# EC_4_Pin_2_0_-_edited.net
KiCad netlist of a schematic drawn in EAGLE
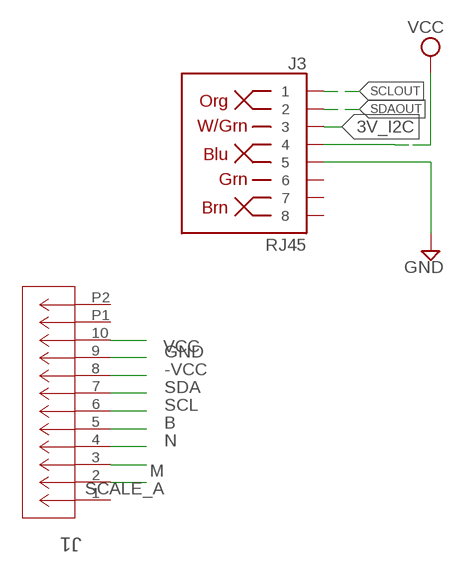
[diagram p0: schematic, sheet 1, part 1 of 2]
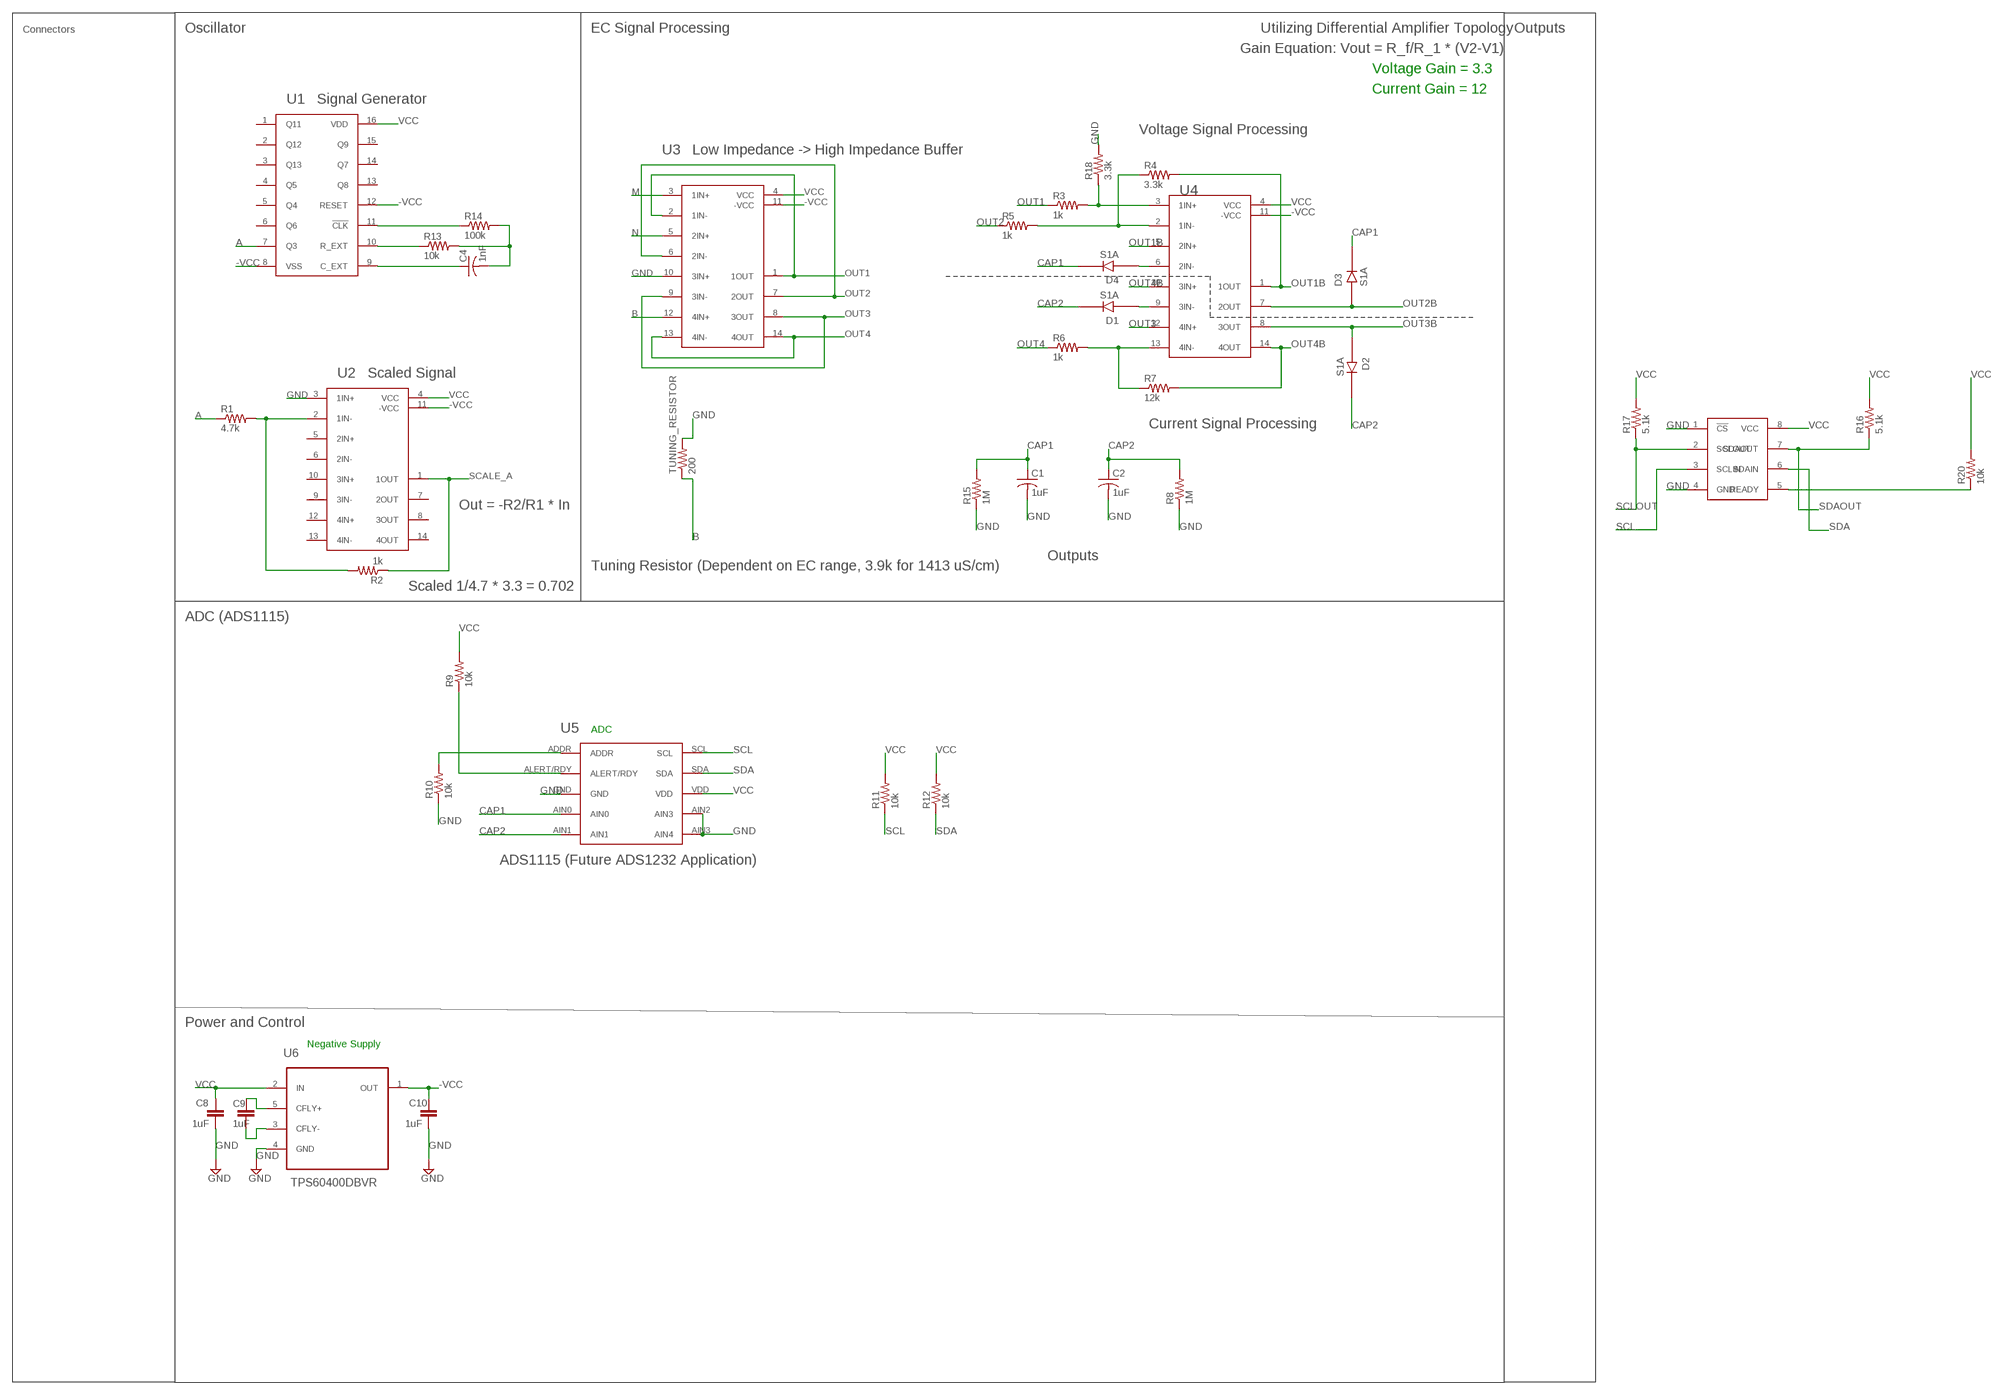
[diagram p1: schematic, sheet 1, part 2 of 2]

(export (version "E")
  (design (tool "Eeschema 10.0.6"))
  (components
    (comp (ref "C1")
      (value "1uF")
      (footprint "eagle-import:C025-024X044")
      (libsource (lib "eagle-import") (part "C-US025-024X044"))
    )
    (comp (ref "C2")
      (value "1uF")
      (footprint "eagle-import:C025-024X044")
      (libsource (lib "eagle-import") (part "C-US025-024X044"))
    )
    (comp (ref "C4")
      (value "1nF")
      (footprint "eagle-import:C1206")
      (libsource (lib "eagle-import") (part "C-USC1206"))
    )
    (comp (ref "C8")
      (value "1uF")
      (footprint "eagle-import:C1206")
      (libsource (lib "eagle-import") (part "C-EUC1206"))
    )
    (comp (ref "C9")
      (value "1uF")
      (footprint "eagle-import:C1206")
      (libsource (lib "eagle-import") (part "C-EUC1206"))
    )
    (comp (ref "C10")
      (value "1uF")
      (footprint "eagle-import:C1206")
      (libsource (lib "eagle-import") (part "C-EUC1206"))
    )
    (comp (ref "D1")
      (value "S1A")
      (footprint "eagle-import:DIOM5227X270N")
      (fields (field (name "DIGI-KEY_PART_NUMBER") "S1AFSTR-ND") (field (name "MF") "ON Semiconductor"))
      (libsource (lib "eagle-import") (part "S1A"))
    )
    (comp (ref "D2")
      (value "S1A")
      (footprint "eagle-import:DIOM5227X270N")
      (fields (field (name "DIGI-KEY_PART_NUMBER") "S1AFSTR-ND") (field (name "MF") "ON Semiconductor"))
      (libsource (lib "eagle-import") (part "S1A"))
    )
    (comp (ref "D3")
      (value "S1A")
      (footprint "eagle-import:DIOM5227X270N")
      (fields (field (name "DIGI-KEY_PART_NUMBER") "S1AFSTR-ND") (field (name "MF") "ON Semiconductor"))
      (libsource (lib "eagle-import") (part "S1A"))
    )
    (comp (ref "D4")
      (value "S1A")
      (footprint "eagle-import:DIOM5227X270N")
      (fields (field (name "DIGI-KEY_PART_NUMBER") "S1AFSTR-ND") (field (name "MF") "ON Semiconductor"))
      (libsource (lib "eagle-import") (part "S1A"))
    )
    (comp (ref "J1")
      (value "522711079")
      (footprint "eagle-import:CON_522711079_MOL")
      (fields (field (name "COPYRIGHT") "Copyright (C) 2023 Ultra Librarian. All rights reserved."))
      (libsource (lib "eagle-import") (part "522711079"))
    )
    (comp (ref "J3")
      (value "RJ45")
      (footprint "eagle-import:RJ45-8")
      (libsource (lib "eagle-import") (part "RJ45-8"))
    )
    (comp (ref "R1")
      (value "4.7k")
      (footprint "eagle-import:M1206")
      (libsource (lib "eagle-import") (part "R-US_M1206"))
    )
    (comp (ref "R2")
      (value "1k")
      (footprint "eagle-import:M1206")
      (libsource (lib "eagle-import") (part "R-US_M1206"))
    )
    (comp (ref "R3")
      (value "1k")
      (footprint "eagle-import:M1206")
      (libsource (lib "eagle-import") (part "R-US_M1206"))
    )
    (comp (ref "R4")
      (value "3.3k")
      (footprint "eagle-import:M1206")
      (libsource (lib "eagle-import") (part "R-US_M1206"))
    )
    (comp (ref "R5")
      (value "1k")
      (footprint "eagle-import:M1206")
      (libsource (lib "eagle-import") (part "R-US_M1206"))
    )
    (comp (ref "R6")
      (value "1k")
      (footprint "eagle-import:M1206")
      (libsource (lib "eagle-import") (part "R-US_M1206"))
    )
    (comp (ref "R7")
      (value "12k")
      (footprint "eagle-import:M1206")
      (libsource (lib "eagle-import") (part "R-US_M1206"))
    )
    (comp (ref "R8")
      (value "1M")
      (footprint "eagle-import:M1206")
      (libsource (lib "eagle-import") (part "R-US_M1206"))
    )
    (comp (ref "R9")
      (value "10k")
      (footprint "eagle-import:M1206")
      (libsource (lib "eagle-import") (part "R-US_M1206"))
    )
    (comp (ref "R10")
      (value "10k")
      (footprint "eagle-import:M1206")
      (libsource (lib "eagle-import") (part "R-US_M1206"))
    )
    (comp (ref "R11")
      (value "10k")
      (footprint "eagle-import:M1206")
      (libsource (lib "eagle-import") (part "R-US_M1206"))
    )
    (comp (ref "R12")
      (value "10k")
      (footprint "eagle-import:M1206")
      (libsource (lib "eagle-import") (part "R-US_M1206"))
    )
    (comp (ref "R13")
      (value "10k")
      (footprint "eagle-import:M1206")
      (libsource (lib "eagle-import") (part "R-US_M1206"))
    )
    (comp (ref "R14")
      (value "100k")
      (footprint "eagle-import:M1206")
      (libsource (lib "eagle-import") (part "R-US_M1206"))
    )
    (comp (ref "R15")
      (value "1M")
      (footprint "eagle-import:M1206")
      (libsource (lib "eagle-import") (part "R-US_M1206"))
    )
    (comp (ref "R16")
      (value "5.1k")
      (footprint "eagle-import:M1206")
      (libsource (lib "eagle-import") (part "R-US_M1206"))
    )
    (comp (ref "R17")
      (value "5.1k")
      (footprint "eagle-import:M1206")
      (libsource (lib "eagle-import") (part "R-US_M1206"))
    )
    (comp (ref "R18")
      (value "3.3k")
      (footprint "eagle-import:M1206")
      (libsource (lib "eagle-import") (part "R-US_M1206"))
    )
    (comp (ref "R20")
      (value "10k")
      (footprint "eagle-import:M1206")
      (libsource (lib "eagle-import") (part "R-US_M1206"))
    )
    (comp (ref "TUNING_RESISTOR")
      (value "200")
      (footprint "eagle-import:M1206")
      (libsource (lib "eagle-import") (part "R-US_M1206"))
    )
    (comp (ref "U$1")
      (value "LTC4301")
      (footprint "eagle-import:LTC4301")
      (libsource (lib "eagle-import") (part "LTC4301"))
    )
    (comp (ref "U1")
      (value "CD4060BPWR")
      (footprint "eagle-import:CD4060BPWR")
      (libsource (lib "eagle-import") (part "CD4060BPWR"))
    )
    (comp (ref "U2")
      (value "TL074CPWR")
      (footprint "eagle-import:LT074CPWR")
      (libsource (lib "eagle-import") (part "TL074CPWR"))
    )
    (comp (ref "U3")
      (value "TL074CPWR")
      (footprint "eagle-import:LT074CPWR")
      (libsource (lib "eagle-import") (part "TL074CPWR"))
    )
    (comp (ref "U4")
      (value "TL074CPWR")
      (footprint "eagle-import:LT074CPWR")
      (libsource (lib "eagle-import") (part "TL074CPWR"))
    )
    (comp (ref "U5")
      (value "ADS1115")
      (footprint "eagle-import:ADS1115")
      (libsource (lib "eagle-import") (part "ADS1115"))
    )
    (comp (ref "U6")
      (value "TPS60400DBVR")
      (footprint "eagle-import:SOT95P280X145-5N")
      (fields (field (name "MF") "Texas Instruments"))
      (libsource (lib "eagle-import") (part "TPS60400DBVR"))
    )
  )
  (nets
    (net (code "1") (name "/-VCC") (class "Default")
      (node (ref "C10") (pin "2") (pinfunction "2_2") (pintype "passive"))
      (node (ref "J1") (pin "8") (pinfunction "8_8") (pintype "passive"))
      (node (ref "U1") (pin "12") (pinfunction "RESET_12") (pintype "bidirectional"))
      (node (ref "U1") (pin "8") (pinfunction "VSS_8") (pintype "bidirectional"))
      (node (ref "U2") (pin "11") (pinfunction "-VCC_11") (pintype "bidirectional"))
      (node (ref "U3") (pin "11") (pinfunction "-VCC_11") (pintype "bidirectional"))
      (node (ref "U4") (pin "11") (pinfunction "-VCC_11") (pintype "bidirectional"))
      (node (ref "U6") (pin "1") (pinfunction "OUT_1") (pintype "output"))
    )
    (net (code "2") (name "/A") (class "Default")
      (node (ref "R1") (pin "1") (pinfunction "1_1") (pintype "passive"))
      (node (ref "U1") (pin "7") (pinfunction "Q3_7") (pintype "bidirectional"))
    )
    (net (code "3") (name "/B") (class "Default")
      (node (ref "J1") (pin "5") (pinfunction "5_5") (pintype "passive"))
      (node (ref "TUNING_RESISTOR") (pin "1") (pinfunction "1_1") (pintype "passive"))
      (node (ref "U3") (pin "12") (pinfunction "4IN+_12") (pintype "bidirectional"))
    )
    (net (code "4") (name "/CAP1") (class "Default")
      (node (ref "C1") (pin "1") (pinfunction "1_1") (pintype "passive"))
      (node (ref "D3") (pin "1") (pinfunction "C_1") (pintype "passive"))
      (node (ref "D4") (pin "1") (pinfunction "C_1") (pintype "passive"))
      (node (ref "R15") (pin "2") (pinfunction "2_2") (pintype "passive"))
      (node (ref "U5") (pin "AIN0") (pinfunction "AIN0_AIN0") (pintype "bidirectional"))
    )
    (net (code "5") (name "/CAP2") (class "Default")
      (node (ref "C2") (pin "1") (pinfunction "1_1") (pintype "passive"))
      (node (ref "D1") (pin "1") (pinfunction "C_1") (pintype "passive"))
      (node (ref "D2") (pin "1") (pinfunction "C_1") (pintype "passive"))
      (node (ref "R8") (pin "2") (pinfunction "2_2") (pintype "passive"))
      (node (ref "U5") (pin "AIN1") (pinfunction "AIN1_AIN1") (pintype "bidirectional"))
    )
    (net (code "6") (name "/M") (class "Default")
      (node (ref "J1") (pin "3") (pinfunction "3_3") (pintype "passive"))
      (node (ref "U3") (pin "3") (pinfunction "1IN+_3") (pintype "bidirectional"))
    )
    (net (code "7") (name "/N") (class "Default")
      (node (ref "J1") (pin "4") (pinfunction "4_4") (pintype "passive"))
      (node (ref "U3") (pin "5") (pinfunction "2IN+_5") (pintype "bidirectional"))
    )
    (net (code "8") (name "/OUT1") (class "Default")
      (node (ref "R3") (pin "1") (pinfunction "1_1") (pintype "passive"))
      (node (ref "U3") (pin "1") (pinfunction "1OUT_1") (pintype "bidirectional"))
      (node (ref "U3") (pin "2") (pinfunction "1IN-_2") (pintype "bidirectional"))
    )
    (net (code "9") (name "/OUT1B") (class "Default")
      (node (ref "R4") (pin "2") (pinfunction "2_2") (pintype "passive"))
      (node (ref "U4") (pin "1") (pinfunction "1OUT_1") (pintype "bidirectional"))
      (node (ref "U4") (pin "5") (pinfunction "2IN+_5") (pintype "bidirectional"))
    )
    (net (code "10") (name "/OUT2") (class "Default")
      (node (ref "R5") (pin "1") (pinfunction "1_1") (pintype "passive"))
      (node (ref "U3") (pin "6") (pinfunction "2IN-_6") (pintype "bidirectional"))
      (node (ref "U3") (pin "7") (pinfunction "2OUT_7") (pintype "bidirectional"))
    )
    (net (code "11") (name "/OUT2B") (class "Default")
      (node (ref "D3") (pin "2") (pinfunction "A_2") (pintype "passive"))
      (node (ref "U4") (pin "7") (pinfunction "2OUT_7") (pintype "bidirectional"))
    )
    (net (code "12") (name "/OUT3") (class "Default")
      (node (ref "U3") (pin "8") (pinfunction "3OUT_8") (pintype "bidirectional"))
      (node (ref "U3") (pin "9") (pinfunction "3IN-_9") (pintype "bidirectional"))
      (node (ref "U4") (pin "12") (pinfunction "4IN+_12") (pintype "bidirectional"))
    )
    (net (code "13") (name "/OUT3B") (class "Default")
      (node (ref "D2") (pin "2") (pinfunction "A_2") (pintype "passive"))
      (node (ref "U4") (pin "8") (pinfunction "3OUT_8") (pintype "bidirectional"))
    )
    (net (code "14") (name "/OUT4") (class "Default")
      (node (ref "R6") (pin "1") (pinfunction "1_1") (pintype "passive"))
      (node (ref "U3") (pin "13") (pinfunction "4IN-_13") (pintype "bidirectional"))
      (node (ref "U3") (pin "14") (pinfunction "4OUT_14") (pintype "bidirectional"))
    )
    (net (code "15") (name "/OUT4B") (class "Default")
      (node (ref "R7") (pin "2") (pinfunction "2_2") (pintype "passive"))
      (node (ref "U4") (pin "10") (pinfunction "3IN+_10") (pintype "bidirectional"))
      (node (ref "U4") (pin "14") (pinfunction "4OUT_14") (pintype "bidirectional"))
    )
    (net (code "16") (name "/SCALE_A") (class "Default")
      (node (ref "J1") (pin "2") (pinfunction "2_2") (pintype "passive"))
      (node (ref "R2") (pin "1") (pinfunction "1_1") (pintype "passive"))
      (node (ref "U2") (pin "1") (pinfunction "1OUT_1") (pintype "bidirectional"))
    )
    (net (code "17") (name "/SCL") (class "Default")
      (node (ref "J1") (pin "6") (pinfunction "6_6") (pintype "passive"))
      (node (ref "R11") (pin "1") (pinfunction "1_1") (pintype "passive"))
      (node (ref "U$1") (pin "3") (pinfunction "SCLIN_3") (pintype "bidirectional"))
      (node (ref "U5") (pin "SCL") (pinfunction "SCL_SCL") (pintype "bidirectional"))
    )
    (net (code "18") (name "/SDA") (class "Default")
      (node (ref "J1") (pin "7") (pinfunction "7_7") (pintype "passive"))
      (node (ref "R12") (pin "1") (pinfunction "1_1") (pintype "passive"))
      (node (ref "U$1") (pin "6") (pinfunction "SDAIN_6") (pintype "bidirectional"))
      (node (ref "U5") (pin "SDA") (pinfunction "SDA_SDA") (pintype "bidirectional"))
    )
    (net (code "19") (name "3V_I2C") (class "Default")
      (node (ref "J3") (pin "3") (pinfunction "3_3") (pintype "bidirectional"))
    )
    (net (code "20") (name "GND") (class "Default")
      (node (ref "C1") (pin "2") (pinfunction "2_2") (pintype "passive"))
      (node (ref "C10") (pin "1") (pinfunction "1_1") (pintype "passive"))
      (node (ref "C2") (pin "2") (pinfunction "2_2") (pintype "passive"))
      (node (ref "C8") (pin "1") (pinfunction "1_1") (pintype "passive"))
      (node (ref "J1") (pin "9") (pinfunction "9_9") (pintype "passive"))
      (node (ref "J3") (pin "5") (pinfunction "5_5") (pintype "bidirectional"))
      (node (ref "R10") (pin "1") (pinfunction "1_1") (pintype "passive"))
      (node (ref "R15") (pin "1") (pinfunction "1_1") (pintype "passive"))
      (node (ref "R18") (pin "2") (pinfunction "2_2") (pintype "passive"))
      (node (ref "R8") (pin "1") (pinfunction "1_1") (pintype "passive"))
      (node (ref "TUNING_RESISTOR") (pin "2") (pinfunction "2_2") (pintype "passive"))
      (node (ref "U$1") (pin "1") (pinfunction "~{CS}_1") (pintype "bidirectional"))
      (node (ref "U$1") (pin "4") (pinfunction "GND_4") (pintype "bidirectional"))
      (node (ref "U2") (pin "3") (pinfunction "1IN+_3") (pintype "bidirectional"))
      (node (ref "U3") (pin "10") (pinfunction "3IN+_10") (pintype "bidirectional"))
      (node (ref "U5") (pin "AIN2") (pinfunction "AIN3_AIN2") (pintype "bidirectional"))
      (node (ref "U5") (pin "AIN3") (pinfunction "AIN4_AIN3") (pintype "bidirectional"))
      (node (ref "U5") (pin "GND") (pinfunction "GND_GND") (pintype "bidirectional"))
      (node (ref "U6") (pin "4") (pinfunction "GND_4") (pintype "passive"))
    )
    (net (code "21") (name "Net-(C4-Pad2)") (class "Default")
      (node (ref "C4") (pin "2") (pinfunction "2_2") (pintype "passive"))
      (node (ref "R13") (pin "2") (pinfunction "2_2") (pintype "passive"))
      (node (ref "R14") (pin "2") (pinfunction "2_2") (pintype "passive"))
    )
    (net (code "22") (name "Net-(D1-A)") (class "Default")
      (node (ref "D1") (pin "2") (pinfunction "A_2") (pintype "passive"))
      (node (ref "U4") (pin "9") (pinfunction "3IN-_9") (pintype "bidirectional"))
    )
    (net (code "23") (name "Net-(D4-A)") (class "Default")
      (node (ref "D4") (pin "2") (pinfunction "A_2") (pintype "passive"))
      (node (ref "U4") (pin "6") (pinfunction "2IN-_6") (pintype "bidirectional"))
    )
    (net (code "24") (name "Net-(R9-Pad1)") (class "Default")
      (node (ref "R9") (pin "1") (pinfunction "1_1") (pintype "passive"))
      (node (ref "U5") (pin "ALERT/RDY") (pinfunction "ALERT/RDY_ALERT/RDY") (pintype "bidirectional"))
    )
    (net (code "25") (name "Net-(R10-Pad2)") (class "Default")
      (node (ref "R10") (pin "2") (pinfunction "2_2") (pintype "passive"))
      (node (ref "U5") (pin "ADDR") (pinfunction "ADDR_ADDR") (pintype "bidirectional"))
    )
    (net (code "26") (name "Net-(U$1-READY)") (class "Default")
      (node (ref "R20") (pin "1") (pinfunction "1_1") (pintype "passive"))
      (node (ref "U$1") (pin "5") (pinfunction "READY_5") (pintype "bidirectional"))
    )
    (net (code "27") (name "Net-(U1-C_EXT)") (class "Default")
      (node (ref "C4") (pin "1") (pinfunction "1_1") (pintype "passive"))
      (node (ref "U1") (pin "9") (pinfunction "C_EXT_9") (pintype "bidirectional"))
    )
    (net (code "28") (name "Net-(U1-R_EXT)") (class "Default")
      (node (ref "R13") (pin "1") (pinfunction "1_1") (pintype "passive"))
      (node (ref "U1") (pin "10") (pinfunction "R_EXT_10") (pintype "bidirectional"))
    )
    (net (code "29") (name "Net-(U1-~{CLK})") (class "Default")
      (node (ref "R14") (pin "1") (pinfunction "1_1") (pintype "passive"))
      (node (ref "U1") (pin "11") (pinfunction "~{CLK}_11") (pintype "bidirectional"))
    )
    (net (code "30") (name "Net-(U2-1IN-)") (class "Default")
      (node (ref "R1") (pin "2") (pinfunction "2_2") (pintype "passive"))
      (node (ref "R2") (pin "2") (pinfunction "2_2") (pintype "passive"))
      (node (ref "U2") (pin "2") (pinfunction "1IN-_2") (pintype "bidirectional"))
    )
    (net (code "31") (name "Net-(U4-1IN+)") (class "Default")
      (node (ref "R18") (pin "1") (pinfunction "1_1") (pintype "passive"))
      (node (ref "R3") (pin "2") (pinfunction "2_2") (pintype "passive"))
      (node (ref "U4") (pin "3") (pinfunction "1IN+_3") (pintype "bidirectional"))
    )
    (net (code "32") (name "Net-(U4-1IN-)") (class "Default")
      (node (ref "R4") (pin "1") (pinfunction "1_1") (pintype "passive"))
      (node (ref "R5") (pin "2") (pinfunction "2_2") (pintype "passive"))
      (node (ref "U4") (pin "2") (pinfunction "1IN-_2") (pintype "bidirectional"))
    )
    (net (code "33") (name "Net-(U4-4IN-)") (class "Default")
      (node (ref "R6") (pin "2") (pinfunction "2_2") (pintype "passive"))
      (node (ref "R7") (pin "1") (pinfunction "1_1") (pintype "passive"))
      (node (ref "U4") (pin "13") (pinfunction "4IN-_13") (pintype "bidirectional"))
    )
    (net (code "34") (name "Net-(U6-CFLY+)") (class "Default")
      (node (ref "C9") (pin "2") (pinfunction "2_2") (pintype "passive"))
      (node (ref "U6") (pin "5") (pinfunction "CFLY+_5") (pintype "input"))
    )
    (net (code "35") (name "Net-(U6-CFLY-)") (class "Default")
      (node (ref "C9") (pin "1") (pinfunction "1_1") (pintype "passive"))
      (node (ref "U6") (pin "3") (pinfunction "CFLY-_3") (pintype "input"))
    )
    (net (code "36") (name "SCLOUT") (class "Default")
      (node (ref "J3") (pin "1") (pinfunction "1_1") (pintype "bidirectional"))
      (node (ref "R17") (pin "1") (pinfunction "1_1") (pintype "passive"))
      (node (ref "U$1") (pin "2") (pinfunction "SCLOUT_2") (pintype "bidirectional"))
    )
    (net (code "37") (name "SDAOUT") (class "Default")
      (node (ref "J3") (pin "2") (pinfunction "2_2") (pintype "bidirectional"))
      (node (ref "R16") (pin "1") (pinfunction "1_1") (pintype "passive"))
      (node (ref "U$1") (pin "7") (pinfunction "SDAOUT_7") (pintype "bidirectional"))
    )
    (net (code "38") (name "VCC") (class "Default")
      (node (ref "C8") (pin "2") (pinfunction "2_2") (pintype "passive"))
      (node (ref "J1") (pin "10") (pinfunction "10_10") (pintype "passive"))
      (node (ref "J3") (pin "4") (pinfunction "4_4") (pintype "bidirectional"))
      (node (ref "R11") (pin "2") (pinfunction "2_2") (pintype "passive"))
      (node (ref "R12") (pin "2") (pinfunction "2_2") (pintype "passive"))
      (node (ref "R16") (pin "2") (pinfunction "2_2") (pintype "passive"))
      (node (ref "R17") (pin "2") (pinfunction "2_2") (pintype "passive"))
      (node (ref "R20") (pin "2") (pinfunction "2_2") (pintype "passive"))
      (node (ref "R9") (pin "2") (pinfunction "2_2") (pintype "passive"))
      (node (ref "U$1") (pin "8") (pinfunction "VCC_8") (pintype "bidirectional"))
      (node (ref "U1") (pin "16") (pinfunction "VDD_16") (pintype "bidirectional"))
      (node (ref "U2") (pin "4") (pinfunction "VCC_4") (pintype "bidirectional"))
      (node (ref "U3") (pin "4") (pinfunction "VCC_4") (pintype "bidirectional"))
      (node (ref "U4") (pin "4") (pinfunction "VCC_4") (pintype "bidirectional"))
      (node (ref "U5") (pin "VDD") (pinfunction "VDD_VDD") (pintype "bidirectional"))
      (node (ref "U6") (pin "2") (pinfunction "IN_2") (pintype "power_in"))
    )
    (net (code "39") (name "unconnected-(J1-Pad1)") (class "Default")
      (node (ref "J1") (pin "1") (pinfunction "1_1") (pintype "passive"))
    )
    (net (code "40") (name "unconnected-(J1-PadP1)") (class "Default")
      (node (ref "J1") (pin "P1") (pinfunction "P1_P1") (pintype "passive"))
    )
    (net (code "41") (name "unconnected-(J1-PadP2)") (class "Default")
      (node (ref "J1") (pin "P2") (pinfunction "P2_P2") (pintype "passive"))
    )
    (net (code "42") (name "unconnected-(J3-Pad6)") (class "Default")
      (node (ref "J3") (pin "6") (pinfunction "6_6") (pintype "bidirectional"))
    )
    (net (code "43") (name "unconnected-(J3-Pad7)") (class "Default")
      (node (ref "J3") (pin "7") (pinfunction "7_7") (pintype "bidirectional"))
    )
    (net (code "44") (name "unconnected-(J3-Pad8)") (class "Default")
      (node (ref "J3") (pin "8") (pinfunction "8_8") (pintype "bidirectional"))
    )
    (net (code "45") (name "unconnected-(U1-Q4-Pad5)") (class "Default")
      (node (ref "U1") (pin "5") (pinfunction "Q4_5") (pintype "bidirectional"))
    )
    (net (code "46") (name "unconnected-(U1-Q5-Pad4)") (class "Default")
      (node (ref "U1") (pin "4") (pinfunction "Q5_4") (pintype "bidirectional"))
    )
    (net (code "47") (name "unconnected-(U1-Q6-Pad6)") (class "Default")
      (node (ref "U1") (pin "6") (pinfunction "Q6_6") (pintype "bidirectional"))
    )
    (net (code "48") (name "unconnected-(U1-Q7-Pad14)") (class "Default")
      (node (ref "U1") (pin "14") (pinfunction "Q7_14") (pintype "bidirectional"))
    )
    (net (code "49") (name "unconnected-(U1-Q8-Pad13)") (class "Default")
      (node (ref "U1") (pin "13") (pinfunction "Q8_13") (pintype "bidirectional"))
    )
    (net (code "50") (name "unconnected-(U1-Q9-Pad15)") (class "Default")
      (node (ref "U1") (pin "15") (pinfunction "Q9_15") (pintype "bidirectional"))
    )
    (net (code "51") (name "unconnected-(U1-Q11-Pad1)") (class "Default")
      (node (ref "U1") (pin "1") (pinfunction "Q11_1") (pintype "bidirectional"))
    )
    (net (code "52") (name "unconnected-(U1-Q12-Pad2)") (class "Default")
      (node (ref "U1") (pin "2") (pinfunction "Q12_2") (pintype "bidirectional"))
    )
    (net (code "53") (name "unconnected-(U1-Q13-Pad3)") (class "Default")
      (node (ref "U1") (pin "3") (pinfunction "Q13_3") (pintype "bidirectional"))
    )
    (net (code "54") (name "unconnected-(U2-2IN+-Pad5)") (class "Default")
      (node (ref "U2") (pin "5") (pinfunction "2IN+_5") (pintype "bidirectional"))
    )
    (net (code "55") (name "unconnected-(U2-2IN--Pad6)") (class "Default")
      (node (ref "U2") (pin "6") (pinfunction "2IN-_6") (pintype "bidirectional"))
    )
    (net (code "56") (name "unconnected-(U2-2OUT-Pad7)") (class "Default")
      (node (ref "U2") (pin "7") (pinfunction "2OUT_7") (pintype "bidirectional"))
    )
    (net (code "57") (name "unconnected-(U2-3IN+-Pad10)") (class "Default")
      (node (ref "U2") (pin "10") (pinfunction "3IN+_10") (pintype "bidirectional"))
    )
    (net (code "58") (name "unconnected-(U2-3IN--Pad9)") (class "Default")
      (node (ref "U2") (pin "9") (pinfunction "3IN-_9") (pintype "bidirectional"))
    )
    (net (code "59") (name "unconnected-(U2-3OUT-Pad8)") (class "Default")
      (node (ref "U2") (pin "8") (pinfunction "3OUT_8") (pintype "bidirectional"))
    )
    (net (code "60") (name "unconnected-(U2-4IN+-Pad12)") (class "Default")
      (node (ref "U2") (pin "12") (pinfunction "4IN+_12") (pintype "bidirectional"))
    )
    (net (code "61") (name "unconnected-(U2-4IN--Pad13)") (class "Default")
      (node (ref "U2") (pin "13") (pinfunction "4IN-_13") (pintype "bidirectional"))
    )
    (net (code "62") (name "unconnected-(U2-4OUT-Pad14)") (class "Default")
      (node (ref "U2") (pin "14") (pinfunction "4OUT_14") (pintype "bidirectional"))
    )
  )
)
